# routing_option1.net
KiCad netlist of a schematic drawn in EAGLE
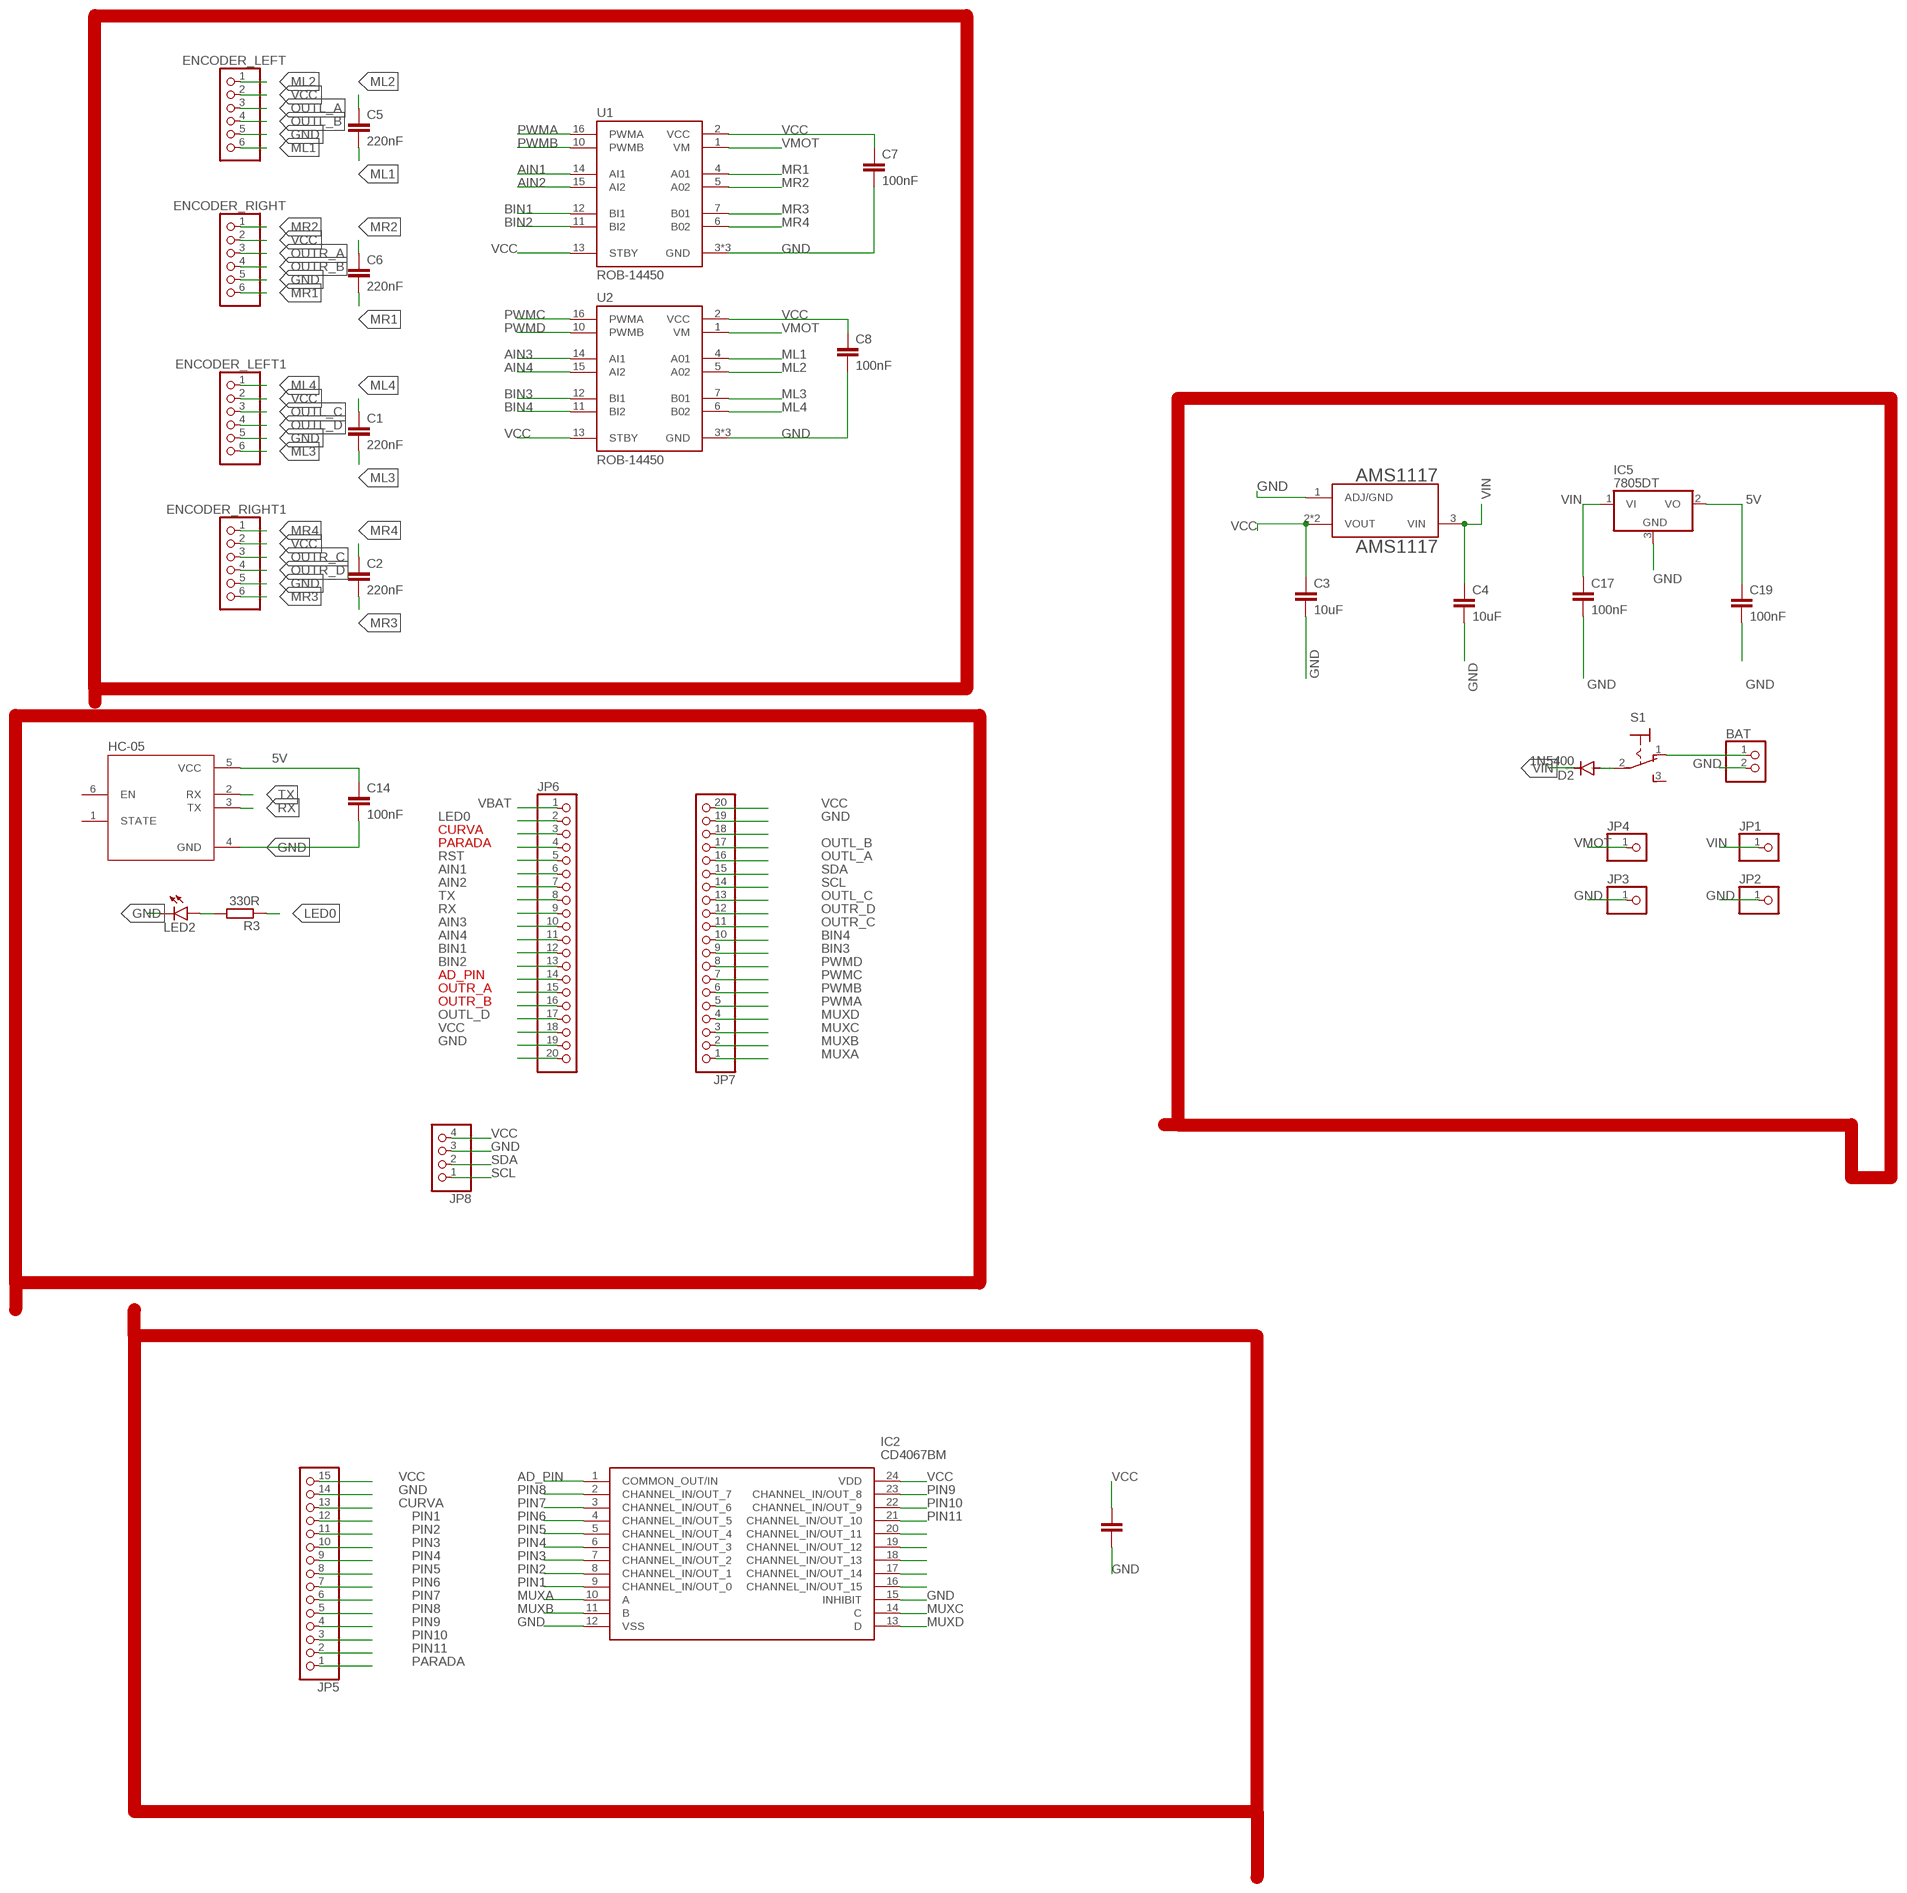
[diagram p0: schematic, sheet 1]

(export (version "E")
  (design (tool "Eeschema 10.0.6"))
  (components
    (comp (ref "AMS1117")
      (value "AMS1117")
      (footprint "eagle-import:SOT229P700X180-4N")
      (fields (field (name "MF") "Advanced Monolithic Systems"))
      (libsource (lib "eagle-import") (part "AMS1117"))
    )
    (comp (ref "BAT")
      (value "PINHD-1X2")
      (footprint "eagle-import:1X02")
      (libsource (lib "eagle-import") (part "PINHD-1X2"))
    )
    (comp (ref "C1")
      (value "220nF")
      (footprint "eagle-import:C0805")
      (libsource (lib "eagle-import") (part "C-EUC0805"))
    )
    (comp (ref "C2")
      (value "220nF")
      (footprint "eagle-import:C0805")
      (libsource (lib "eagle-import") (part "C-EUC0805"))
    )
    (comp (ref "C3")
      (value "10uF")
      (footprint "eagle-import:C0805")
      (libsource (lib "eagle-import") (part "C-EUC0805"))
    )
    (comp (ref "C4")
      (value "10uF")
      (footprint "eagle-import:C0805")
      (libsource (lib "eagle-import") (part "C-EUC0805"))
    )
    (comp (ref "C5")
      (value "220nF")
      (footprint "eagle-import:C0805")
      (libsource (lib "eagle-import") (part "C-EUC0805"))
    )
    (comp (ref "C6")
      (value "220nF")
      (footprint "eagle-import:C0805")
      (libsource (lib "eagle-import") (part "C-EUC0805"))
    )
    (comp (ref "C7")
      (value "100nF")
      (footprint "eagle-import:C0805")
      (libsource (lib "eagle-import") (part "C-EUC0805"))
    )
    (comp (ref "C8")
      (value "100nF")
      (footprint "eagle-import:C0805")
      (libsource (lib "eagle-import") (part "C-EUC0805"))
    )
    (comp (ref "C10")
      (value "100nF")
      (footprint "eagle-import:C0805")
      (libsource (lib "eagle-import") (part "C-EUC0805"))
    )
    (comp (ref "C14")
      (value "100nF")
      (footprint "eagle-import:C0805")
      (libsource (lib "eagle-import") (part "C-EUC0805"))
    )
    (comp (ref "C17")
      (value "100nF")
      (footprint "eagle-import:C0805")
      (libsource (lib "eagle-import") (part "C-EUC0805"))
    )
    (comp (ref "C19")
      (value "100nF")
      (footprint "eagle-import:C0805")
      (libsource (lib "eagle-import") (part "C-EUC0805"))
    )
    (comp (ref "D2")
      (value "1N5400")
      (footprint "eagle-import:DO201-15")
      (libsource (lib "eagle-import") (part "1N5400"))
    )
    (comp (ref "ENCODER_LEFT")
      (value "PINHD-1X6")
      (footprint "eagle-import:1X06")
      (libsource (lib "eagle-import") (part "PINHD-1X6"))
    )
    (comp (ref "ENCODER_LEFT1")
      (value "PINHD-1X6")
      (footprint "eagle-import:1X06")
      (libsource (lib "eagle-import") (part "PINHD-1X6"))
    )
    (comp (ref "ENCODER_RIGHT")
      (value "PINHD-1X6")
      (footprint "eagle-import:1X06")
      (libsource (lib "eagle-import") (part "PINHD-1X6"))
    )
    (comp (ref "ENCODER_RIGHT1")
      (value "PINHD-1X6")
      (footprint "eagle-import:1X06")
      (libsource (lib "eagle-import") (part "PINHD-1X6"))
    )
    (comp (ref "HC-05")
      (value "ZC142200")
      (footprint "eagle-import:MODULE_ZC142200")
      (fields (field (name "MF") "YKS"))
      (libsource (lib "eagle-import") (part "ZC142200"))
    )
    (comp (ref "IC2")
      (value "CD4067BM")
      (footprint "eagle-import:SOIC127P1030X265-24N")
      (fields (field (name "MOUSER_PART_NUMBER") "595-CD4067BM"))
      (libsource (lib "eagle-import") (part "CD4067BM"))
    )
    (comp (ref "IC5")
      (value "7805DT")
      (footprint "eagle-import:TO252")
      (libsource (lib "eagle-import") (part "78DT05"))
    )
    (comp (ref "JP1")
      (value "PINHD-1X1")
      (footprint "eagle-import:1X01")
      (libsource (lib "eagle-import") (part "PINHD-1X1"))
    )
    (comp (ref "JP2")
      (value "PINHD-1X1")
      (footprint "eagle-import:1X01")
      (libsource (lib "eagle-import") (part "PINHD-1X1"))
    )
    (comp (ref "JP3")
      (value "PINHD-1X1")
      (footprint "eagle-import:1X01")
      (libsource (lib "eagle-import") (part "PINHD-1X1"))
    )
    (comp (ref "JP4")
      (value "PINHD-1X1")
      (footprint "eagle-import:1X01")
      (libsource (lib "eagle-import") (part "PINHD-1X1"))
    )
    (comp (ref "JP5")
      (value "PINHD-1X15")
      (footprint "eagle-import:1X15")
      (libsource (lib "eagle-import") (part "PINHD-1X15"))
    )
    (comp (ref "JP6")
      (value "PINHD-1X20")
      (footprint "eagle-import:1X20")
      (libsource (lib "eagle-import") (part "PINHD-1X20"))
    )
    (comp (ref "JP7")
      (value "PINHD-1X20")
      (footprint "eagle-import:1X20")
      (libsource (lib "eagle-import") (part "PINHD-1X20"))
    )
    (comp (ref "JP8")
      (value "PINHD-1X4")
      (footprint "eagle-import:1X04")
      (libsource (lib "eagle-import") (part "PINHD-1X4"))
    )
    (comp (ref "LED2")
      (value "LEDCHIPLED_0805")
      (footprint "eagle-import:CHIPLED_0805")
      (libsource (lib "eagle-import") (part "LEDCHIPLED_0805"))
    )
    (comp (ref "R3")
      (value "330R")
      (footprint "eagle-import:R0805")
      (libsource (lib "eagle-import") (part "R-EU_R0805"))
    )
    (comp (ref "S1")
      (value "320-916")
      (footprint "eagle-import:320-916")
      (libsource (lib "eagle-import") (part "320-916"))
    )
    (comp (ref "U1")
      (value "ROB-14450")
      (footprint "eagle-import:MODULE_ROB-14450")
      (fields (field (name "MF") "SparkFun Electronics"))
      (libsource (lib "eagle-import") (part "ROB-14450"))
    )
    (comp (ref "U2")
      (value "ROB-14450")
      (footprint "eagle-import:MODULE_ROB-14450")
      (fields (field (name "MF") "SparkFun Electronics"))
      (libsource (lib "eagle-import") (part "ROB-14450"))
    )
  )
  (nets
    (net (code "1") (name "/5V") (class "Default")
      (node (ref "C14") (pin "1") (pinfunction "1_1") (pintype "passive"))
      (node (ref "C19") (pin "1") (pinfunction "1_1") (pintype "passive"))
      (node (ref "HC-05") (pin "5") (pinfunction "VCC_5") (pintype "power_in"))
      (node (ref "IC5") (pin "2") (pinfunction "VO_2") (pintype "passive"))
    )
    (net (code "2") (name "/AD_PIN") (class "Default")
      (node (ref "IC2") (pin "1") (pinfunction "COMMON_OUT/IN_1") (pintype "bidirectional"))
      (node (ref "JP6") (pin "14") (pinfunction "14_14") (pintype "passive"))
    )
    (net (code "3") (name "/AIN1") (class "Default")
      (node (ref "JP6") (pin "6") (pinfunction "6_6") (pintype "passive"))
      (node (ref "U1") (pin "14") (pinfunction "AI1_14") (pintype "input"))
    )
    (net (code "4") (name "/AIN2") (class "Default")
      (node (ref "JP6") (pin "7") (pinfunction "7_7") (pintype "passive"))
      (node (ref "U1") (pin "15") (pinfunction "AI2_15") (pintype "input"))
    )
    (net (code "5") (name "/AIN3") (class "Default")
      (node (ref "JP6") (pin "10") (pinfunction "10_10") (pintype "passive"))
      (node (ref "U2") (pin "14") (pinfunction "AI1_14") (pintype "input"))
    )
    (net (code "6") (name "/AIN4") (class "Default")
      (node (ref "JP6") (pin "11") (pinfunction "11_11") (pintype "passive"))
      (node (ref "U2") (pin "15") (pinfunction "AI2_15") (pintype "input"))
    )
    (net (code "7") (name "/BIN1") (class "Default")
      (node (ref "JP6") (pin "12") (pinfunction "12_12") (pintype "passive"))
      (node (ref "U1") (pin "12") (pinfunction "BI1_12") (pintype "input"))
    )
    (net (code "8") (name "/BIN2") (class "Default")
      (node (ref "JP6") (pin "13") (pinfunction "13_13") (pintype "passive"))
      (node (ref "U1") (pin "11") (pinfunction "BI2_11") (pintype "input"))
    )
    (net (code "9") (name "/BIN3") (class "Default")
      (node (ref "JP7") (pin "9") (pinfunction "9_9") (pintype "passive"))
      (node (ref "U2") (pin "12") (pinfunction "BI1_12") (pintype "input"))
    )
    (net (code "10") (name "/BIN4") (class "Default")
      (node (ref "JP7") (pin "10") (pinfunction "10_10") (pintype "passive"))
      (node (ref "U2") (pin "11") (pinfunction "BI2_11") (pintype "input"))
    )
    (net (code "11") (name "/CURVA") (class "Default")
      (node (ref "JP5") (pin "13") (pinfunction "13_13") (pintype "passive"))
      (node (ref "JP6") (pin "3") (pinfunction "3_3") (pintype "passive"))
    )
    (net (code "12") (name "/MUXA") (class "Default")
      (node (ref "IC2") (pin "10") (pinfunction "A_10") (pintype "bidirectional"))
      (node (ref "JP7") (pin "1") (pinfunction "1_1") (pintype "passive"))
    )
    (net (code "13") (name "/MUXB") (class "Default")
      (node (ref "IC2") (pin "11") (pinfunction "B_11") (pintype "bidirectional"))
      (node (ref "JP7") (pin "2") (pinfunction "2_2") (pintype "passive"))
    )
    (net (code "14") (name "/MUXC") (class "Default")
      (node (ref "IC2") (pin "14") (pinfunction "C_14") (pintype "bidirectional"))
      (node (ref "JP7") (pin "3") (pinfunction "3_3") (pintype "passive"))
    )
    (net (code "15") (name "/MUXD") (class "Default")
      (node (ref "IC2") (pin "13") (pinfunction "D_13") (pintype "bidirectional"))
      (node (ref "JP7") (pin "4") (pinfunction "4_4") (pintype "passive"))
    )
    (net (code "16") (name "/PARADA") (class "Default")
      (node (ref "JP5") (pin "1") (pinfunction "1_1") (pintype "passive"))
      (node (ref "JP6") (pin "4") (pinfunction "4_4") (pintype "passive"))
    )
    (net (code "17") (name "/PIN1") (class "Default")
      (node (ref "IC2") (pin "9") (pinfunction "CHANNEL_IN/OUT_0_9") (pintype "bidirectional"))
      (node (ref "JP5") (pin "12") (pinfunction "12_12") (pintype "passive"))
    )
    (net (code "18") (name "/PIN2") (class "Default")
      (node (ref "IC2") (pin "8") (pinfunction "CHANNEL_IN/OUT_1_8") (pintype "bidirectional"))
      (node (ref "JP5") (pin "11") (pinfunction "11_11") (pintype "passive"))
    )
    (net (code "19") (name "/PIN3") (class "Default")
      (node (ref "IC2") (pin "7") (pinfunction "CHANNEL_IN/OUT_2_7") (pintype "bidirectional"))
      (node (ref "JP5") (pin "10") (pinfunction "10_10") (pintype "passive"))
    )
    (net (code "20") (name "/PIN4") (class "Default")
      (node (ref "IC2") (pin "6") (pinfunction "CHANNEL_IN/OUT_3_6") (pintype "bidirectional"))
      (node (ref "JP5") (pin "9") (pinfunction "9_9") (pintype "passive"))
    )
    (net (code "21") (name "/PIN5") (class "Default")
      (node (ref "IC2") (pin "5") (pinfunction "CHANNEL_IN/OUT_4_5") (pintype "bidirectional"))
      (node (ref "JP5") (pin "8") (pinfunction "8_8") (pintype "passive"))
    )
    (net (code "22") (name "/PIN6") (class "Default")
      (node (ref "IC2") (pin "4") (pinfunction "CHANNEL_IN/OUT_5_4") (pintype "bidirectional"))
      (node (ref "JP5") (pin "7") (pinfunction "7_7") (pintype "passive"))
    )
    (net (code "23") (name "/PIN7") (class "Default")
      (node (ref "IC2") (pin "3") (pinfunction "CHANNEL_IN/OUT_6_3") (pintype "bidirectional"))
      (node (ref "JP5") (pin "6") (pinfunction "6_6") (pintype "passive"))
    )
    (net (code "24") (name "/PIN8") (class "Default")
      (node (ref "IC2") (pin "2") (pinfunction "CHANNEL_IN/OUT_7_2") (pintype "bidirectional"))
      (node (ref "JP5") (pin "5") (pinfunction "5_5") (pintype "passive"))
    )
    (net (code "25") (name "/PIN9") (class "Default")
      (node (ref "IC2") (pin "23") (pinfunction "CHANNEL_IN/OUT_8_23") (pintype "bidirectional"))
      (node (ref "JP5") (pin "4") (pinfunction "4_4") (pintype "passive"))
    )
    (net (code "26") (name "/PIN10") (class "Default")
      (node (ref "IC2") (pin "22") (pinfunction "CHANNEL_IN/OUT_9_22") (pintype "bidirectional"))
      (node (ref "JP5") (pin "3") (pinfunction "3_3") (pintype "passive"))
    )
    (net (code "27") (name "/PIN11") (class "Default")
      (node (ref "IC2") (pin "21") (pinfunction "CHANNEL_IN/OUT_10_21") (pintype "bidirectional"))
      (node (ref "JP5") (pin "2") (pinfunction "2_2") (pintype "passive"))
    )
    (net (code "28") (name "/PWMA") (class "Default")
      (node (ref "JP7") (pin "5") (pinfunction "5_5") (pintype "passive"))
      (node (ref "U1") (pin "16") (pinfunction "PWMA_16") (pintype "input"))
    )
    (net (code "29") (name "/PWMB") (class "Default")
      (node (ref "JP7") (pin "6") (pinfunction "6_6") (pintype "passive"))
      (node (ref "U1") (pin "10") (pinfunction "PWMB_10") (pintype "input"))
    )
    (net (code "30") (name "/PWMC") (class "Default")
      (node (ref "JP7") (pin "7") (pinfunction "7_7") (pintype "passive"))
      (node (ref "U2") (pin "16") (pinfunction "PWMA_16") (pintype "input"))
    )
    (net (code "31") (name "/PWMD") (class "Default")
      (node (ref "JP7") (pin "8") (pinfunction "8_8") (pintype "passive"))
      (node (ref "U2") (pin "10") (pinfunction "PWMB_10") (pintype "input"))
    )
    (net (code "32") (name "/RST") (class "Default")
      (node (ref "JP6") (pin "5") (pinfunction "5_5") (pintype "passive"))
    )
    (net (code "33") (name "/SCL") (class "Default")
      (node (ref "JP7") (pin "14") (pinfunction "14_14") (pintype "passive"))
      (node (ref "JP8") (pin "1") (pinfunction "1_1") (pintype "passive"))
    )
    (net (code "34") (name "/SDA") (class "Default")
      (node (ref "JP7") (pin "15") (pinfunction "15_15") (pintype "passive"))
      (node (ref "JP8") (pin "2") (pinfunction "2_2") (pintype "passive"))
    )
    (net (code "35") (name "/VBAT") (class "Default")
      (node (ref "JP6") (pin "1") (pinfunction "1_1") (pintype "passive"))
    )
    (net (code "36") (name "/VMOT") (class "Default")
      (node (ref "JP4") (pin "1") (pinfunction "1_1") (pintype "passive"))
      (node (ref "U1") (pin "1") (pinfunction "VM_1") (pintype "power_in"))
      (node (ref "U2") (pin "1") (pinfunction "VM_1") (pintype "power_in"))
    )
    (net (code "37") (name "GND") (class "Default")
      (node (ref "AMS1117") (pin "1") (pinfunction "ADJ/GND_1") (pintype "power_in"))
      (node (ref "BAT") (pin "2") (pinfunction "2_2") (pintype "passive"))
      (node (ref "C10") (pin "2") (pinfunction "2_2") (pintype "passive"))
      (node (ref "C14") (pin "2") (pinfunction "2_2") (pintype "passive"))
      (node (ref "C17") (pin "2") (pinfunction "2_2") (pintype "passive"))
      (node (ref "C19") (pin "2") (pinfunction "2_2") (pintype "passive"))
      (node (ref "C3") (pin "2") (pinfunction "2_2") (pintype "passive"))
      (node (ref "C4") (pin "2") (pinfunction "2_2") (pintype "passive"))
      (node (ref "C7") (pin "2") (pinfunction "2_2") (pintype "passive"))
      (node (ref "C8") (pin "2") (pinfunction "2_2") (pintype "passive"))
      (node (ref "ENCODER_LEFT") (pin "5") (pinfunction "5_5") (pintype "passive"))
      (node (ref "ENCODER_LEFT1") (pin "5") (pinfunction "5_5") (pintype "passive"))
      (node (ref "ENCODER_RIGHT") (pin "5") (pinfunction "5_5") (pintype "passive"))
      (node (ref "ENCODER_RIGHT1") (pin "5") (pinfunction "5_5") (pintype "passive"))
      (node (ref "HC-05") (pin "4") (pinfunction "GND_4") (pintype "power_in"))
      (node (ref "IC2") (pin "12") (pinfunction "VSS_12") (pintype "bidirectional"))
      (node (ref "IC2") (pin "15") (pinfunction "INHIBIT_15") (pintype "bidirectional"))
      (node (ref "IC5") (pin "3") (pinfunction "GND_3") (pintype "passive"))
      (node (ref "JP2") (pin "1") (pinfunction "1_1") (pintype "passive"))
      (node (ref "JP3") (pin "1") (pinfunction "1_1") (pintype "passive"))
      (node (ref "JP5") (pin "14") (pinfunction "14_14") (pintype "passive"))
      (node (ref "JP6") (pin "19") (pinfunction "19_19") (pintype "passive"))
      (node (ref "JP7") (pin "19") (pinfunction "19_19") (pintype "passive"))
      (node (ref "JP8") (pin "3") (pinfunction "3_3") (pintype "passive"))
      (node (ref "LED2") (pin "C") (pinfunction "C_C") (pintype "passive"))
      (node (ref "U1") (pin "3") (pinfunction "GND_3") (pintype "power_in"))
      (node (ref "U1") (pin "8") (pinfunction "GND_8") (pintype "power_in"))
      (node (ref "U1") (pin "9") (pinfunction "GND_9") (pintype "power_in"))
      (node (ref "U2") (pin "3") (pinfunction "GND_3") (pintype "power_in"))
      (node (ref "U2") (pin "8") (pinfunction "GND_8") (pintype "power_in"))
      (node (ref "U2") (pin "9") (pinfunction "GND_9") (pintype "power_in"))
    )
    (net (code "38") (name "LED0") (class "Default")
      (node (ref "JP6") (pin "2") (pinfunction "2_2") (pintype "passive"))
      (node (ref "R3") (pin "1") (pinfunction "1_1") (pintype "passive"))
    )
    (net (code "39") (name "ML1") (class "Default")
      (node (ref "C5") (pin "2") (pinfunction "2_2") (pintype "passive"))
      (node (ref "ENCODER_LEFT") (pin "6") (pinfunction "6_6") (pintype "passive"))
      (node (ref "U2") (pin "4") (pinfunction "A01_4") (pintype "output"))
    )
    (net (code "40") (name "ML2") (class "Default")
      (node (ref "C5") (pin "1") (pinfunction "1_1") (pintype "passive"))
      (node (ref "ENCODER_LEFT") (pin "1") (pinfunction "1_1") (pintype "passive"))
      (node (ref "U2") (pin "5") (pinfunction "A02_5") (pintype "output"))
    )
    (net (code "41") (name "ML3") (class "Default")
      (node (ref "C1") (pin "2") (pinfunction "2_2") (pintype "passive"))
      (node (ref "ENCODER_LEFT1") (pin "6") (pinfunction "6_6") (pintype "passive"))
      (node (ref "U2") (pin "7") (pinfunction "B01_7") (pintype "output"))
    )
    (net (code "42") (name "ML4") (class "Default")
      (node (ref "C1") (pin "1") (pinfunction "1_1") (pintype "passive"))
      (node (ref "ENCODER_LEFT1") (pin "1") (pinfunction "1_1") (pintype "passive"))
      (node (ref "U2") (pin "6") (pinfunction "B02_6") (pintype "output"))
    )
    (net (code "43") (name "MR1") (class "Default")
      (node (ref "C6") (pin "2") (pinfunction "2_2") (pintype "passive"))
      (node (ref "ENCODER_RIGHT") (pin "6") (pinfunction "6_6") (pintype "passive"))
      (node (ref "U1") (pin "4") (pinfunction "A01_4") (pintype "output"))
    )
    (net (code "44") (name "MR2") (class "Default")
      (node (ref "C6") (pin "1") (pinfunction "1_1") (pintype "passive"))
      (node (ref "ENCODER_RIGHT") (pin "1") (pinfunction "1_1") (pintype "passive"))
      (node (ref "U1") (pin "5") (pinfunction "A02_5") (pintype "output"))
    )
    (net (code "45") (name "MR3") (class "Default")
      (node (ref "C2") (pin "2") (pinfunction "2_2") (pintype "passive"))
      (node (ref "ENCODER_RIGHT1") (pin "6") (pinfunction "6_6") (pintype "passive"))
      (node (ref "U1") (pin "7") (pinfunction "B01_7") (pintype "output"))
    )
    (net (code "46") (name "MR4") (class "Default")
      (node (ref "C2") (pin "1") (pinfunction "1_1") (pintype "passive"))
      (node (ref "ENCODER_RIGHT1") (pin "1") (pinfunction "1_1") (pintype "passive"))
      (node (ref "U1") (pin "6") (pinfunction "B02_6") (pintype "output"))
    )
    (net (code "47") (name "Net-(LED2-PadA)") (class "Default")
      (node (ref "LED2") (pin "A") (pinfunction "A_A") (pintype "passive"))
      (node (ref "R3") (pin "2") (pinfunction "2_2") (pintype "passive"))
    )
    (net (code "48") (name "Net-(S1-O)") (class "Default")
      (node (ref "BAT") (pin "1") (pinfunction "1_1") (pintype "passive"))
      (node (ref "S1") (pin "1") (pinfunction "O_1") (pintype "passive"))
    )
    (net (code "49") (name "Net-(S1-P)") (class "Default")
      (node (ref "D2") (pin "A") (pinfunction "A_A") (pintype "passive"))
      (node (ref "S1") (pin "2") (pinfunction "P_2") (pintype "passive"))
    )
    (net (code "50") (name "OUTL_A") (class "Default")
      (node (ref "ENCODER_LEFT") (pin "3") (pinfunction "3_3") (pintype "passive"))
      (node (ref "JP7") (pin "16") (pinfunction "16_16") (pintype "passive"))
    )
    (net (code "51") (name "OUTL_B") (class "Default")
      (node (ref "ENCODER_LEFT") (pin "4") (pinfunction "4_4") (pintype "passive"))
      (node (ref "JP7") (pin "17") (pinfunction "17_17") (pintype "passive"))
    )
    (net (code "52") (name "OUTL_C") (class "Default")
      (node (ref "ENCODER_LEFT1") (pin "3") (pinfunction "3_3") (pintype "passive"))
      (node (ref "JP7") (pin "13") (pinfunction "13_13") (pintype "passive"))
    )
    (net (code "53") (name "OUTL_D") (class "Default")
      (node (ref "ENCODER_LEFT1") (pin "4") (pinfunction "4_4") (pintype "passive"))
      (node (ref "JP6") (pin "17") (pinfunction "17_17") (pintype "passive"))
    )
    (net (code "54") (name "OUTR_A") (class "Default")
      (node (ref "ENCODER_RIGHT") (pin "3") (pinfunction "3_3") (pintype "passive"))
      (node (ref "JP6") (pin "15") (pinfunction "15_15") (pintype "passive"))
    )
    (net (code "55") (name "OUTR_B") (class "Default")
      (node (ref "ENCODER_RIGHT") (pin "4") (pinfunction "4_4") (pintype "passive"))
      (node (ref "JP6") (pin "16") (pinfunction "16_16") (pintype "passive"))
    )
    (net (code "56") (name "OUTR_C") (class "Default")
      (node (ref "ENCODER_RIGHT1") (pin "3") (pinfunction "3_3") (pintype "passive"))
      (node (ref "JP7") (pin "11") (pinfunction "11_11") (pintype "passive"))
    )
    (net (code "57") (name "OUTR_D") (class "Default")
      (node (ref "ENCODER_RIGHT1") (pin "4") (pinfunction "4_4") (pintype "passive"))
      (node (ref "JP7") (pin "12") (pinfunction "12_12") (pintype "passive"))
    )
    (net (code "58") (name "RX") (class "Default")
      (node (ref "HC-05") (pin "3") (pinfunction "TX_3") (pintype "output"))
      (node (ref "JP6") (pin "9") (pinfunction "9_9") (pintype "passive"))
    )
    (net (code "59") (name "TX") (class "Default")
      (node (ref "HC-05") (pin "2") (pinfunction "RX_2") (pintype "input"))
      (node (ref "JP6") (pin "8") (pinfunction "8_8") (pintype "passive"))
    )
    (net (code "60") (name "VCC") (class "Default")
      (node (ref "AMS1117") (pin "2") (pinfunction "VOUT_2") (pintype "output"))
      (node (ref "AMS1117") (pin "4") (pinfunction "VOUT_4") (pintype "output"))
      (node (ref "C10") (pin "1") (pinfunction "1_1") (pintype "passive"))
      (node (ref "C3") (pin "1") (pinfunction "1_1") (pintype "passive"))
      (node (ref "C7") (pin "1") (pinfunction "1_1") (pintype "passive"))
      (node (ref "C8") (pin "1") (pinfunction "1_1") (pintype "passive"))
      (node (ref "ENCODER_LEFT") (pin "2") (pinfunction "2_2") (pintype "passive"))
      (node (ref "ENCODER_LEFT1") (pin "2") (pinfunction "2_2") (pintype "passive"))
      (node (ref "ENCODER_RIGHT") (pin "2") (pinfunction "2_2") (pintype "passive"))
      (node (ref "ENCODER_RIGHT1") (pin "2") (pinfunction "2_2") (pintype "passive"))
      (node (ref "IC2") (pin "24") (pinfunction "VDD_24") (pintype "bidirectional"))
      (node (ref "JP5") (pin "15") (pinfunction "15_15") (pintype "passive"))
      (node (ref "JP6") (pin "18") (pinfunction "18_18") (pintype "passive"))
      (node (ref "JP7") (pin "20") (pinfunction "20_20") (pintype "passive"))
      (node (ref "JP8") (pin "4") (pinfunction "4_4") (pintype "passive"))
      (node (ref "U1") (pin "13") (pinfunction "STBY_13") (pintype "input"))
      (node (ref "U1") (pin "2") (pinfunction "VCC_2") (pintype "power_in"))
      (node (ref "U2") (pin "13") (pinfunction "STBY_13") (pintype "input"))
      (node (ref "U2") (pin "2") (pinfunction "VCC_2") (pintype "power_in"))
    )
    (net (code "61") (name "VIN") (class "Default")
      (node (ref "AMS1117") (pin "3") (pinfunction "VIN_3") (pintype "input"))
      (node (ref "C17") (pin "1") (pinfunction "1_1") (pintype "passive"))
      (node (ref "C4") (pin "1") (pinfunction "1_1") (pintype "passive"))
      (node (ref "D2") (pin "C") (pinfunction "C_C") (pintype "passive"))
      (node (ref "IC5") (pin "1") (pinfunction "VI_1") (pintype "input"))
      (node (ref "JP1") (pin "1") (pinfunction "1_1") (pintype "passive"))
    )
    (net (code "62") (name "unconnected-(HC-05-EN-Pad6)") (class "Default")
      (node (ref "HC-05") (pin "6") (pinfunction "EN_6") (pintype "input"))
    )
    (net (code "63") (name "unconnected-(HC-05-STATE-Pad1)") (class "Default")
      (node (ref "HC-05") (pin "1") (pinfunction "STATE_1") (pintype "input"))
    )
    (net (code "64") (name "unconnected-(IC2-CHANNEL_IN{slash}OUT_11-Pad20)") (class "Default")
      (node (ref "IC2") (pin "20") (pinfunction "CHANNEL_IN/OUT_11_20") (pintype "bidirectional"))
    )
    (net (code "65") (name "unconnected-(IC2-CHANNEL_IN{slash}OUT_12-Pad19)") (class "Default")
      (node (ref "IC2") (pin "19") (pinfunction "CHANNEL_IN/OUT_12_19") (pintype "bidirectional"))
    )
    (net (code "66") (name "unconnected-(IC2-CHANNEL_IN{slash}OUT_13-Pad18)") (class "Default")
      (node (ref "IC2") (pin "18") (pinfunction "CHANNEL_IN/OUT_13_18") (pintype "bidirectional"))
    )
    (net (code "67") (name "unconnected-(IC2-CHANNEL_IN{slash}OUT_14-Pad17)") (class "Default")
      (node (ref "IC2") (pin "17") (pinfunction "CHANNEL_IN/OUT_14_17") (pintype "bidirectional"))
    )
    (net (code "68") (name "unconnected-(IC2-CHANNEL_IN{slash}OUT_15-Pad16)") (class "Default")
      (node (ref "IC2") (pin "16") (pinfunction "CHANNEL_IN/OUT_15_16") (pintype "bidirectional"))
    )
    (net (code "69") (name "unconnected-(JP6-Pad20)") (class "Default")
      (node (ref "JP6") (pin "20") (pinfunction "20_20") (pintype "passive"))
    )
    (net (code "70") (name "unconnected-(JP7-Pad18)") (class "Default")
      (node (ref "JP7") (pin "18") (pinfunction "18_18") (pintype "passive"))
    )
    (net (code "71") (name "unconnected-(S1-S-Pad3)") (class "Default")
      (node (ref "S1") (pin "3") (pinfunction "S_3") (pintype "passive"))
    )
  )
)
